# Peripherals.net
KiCad netlist of a schematic drawn in Altium Designer
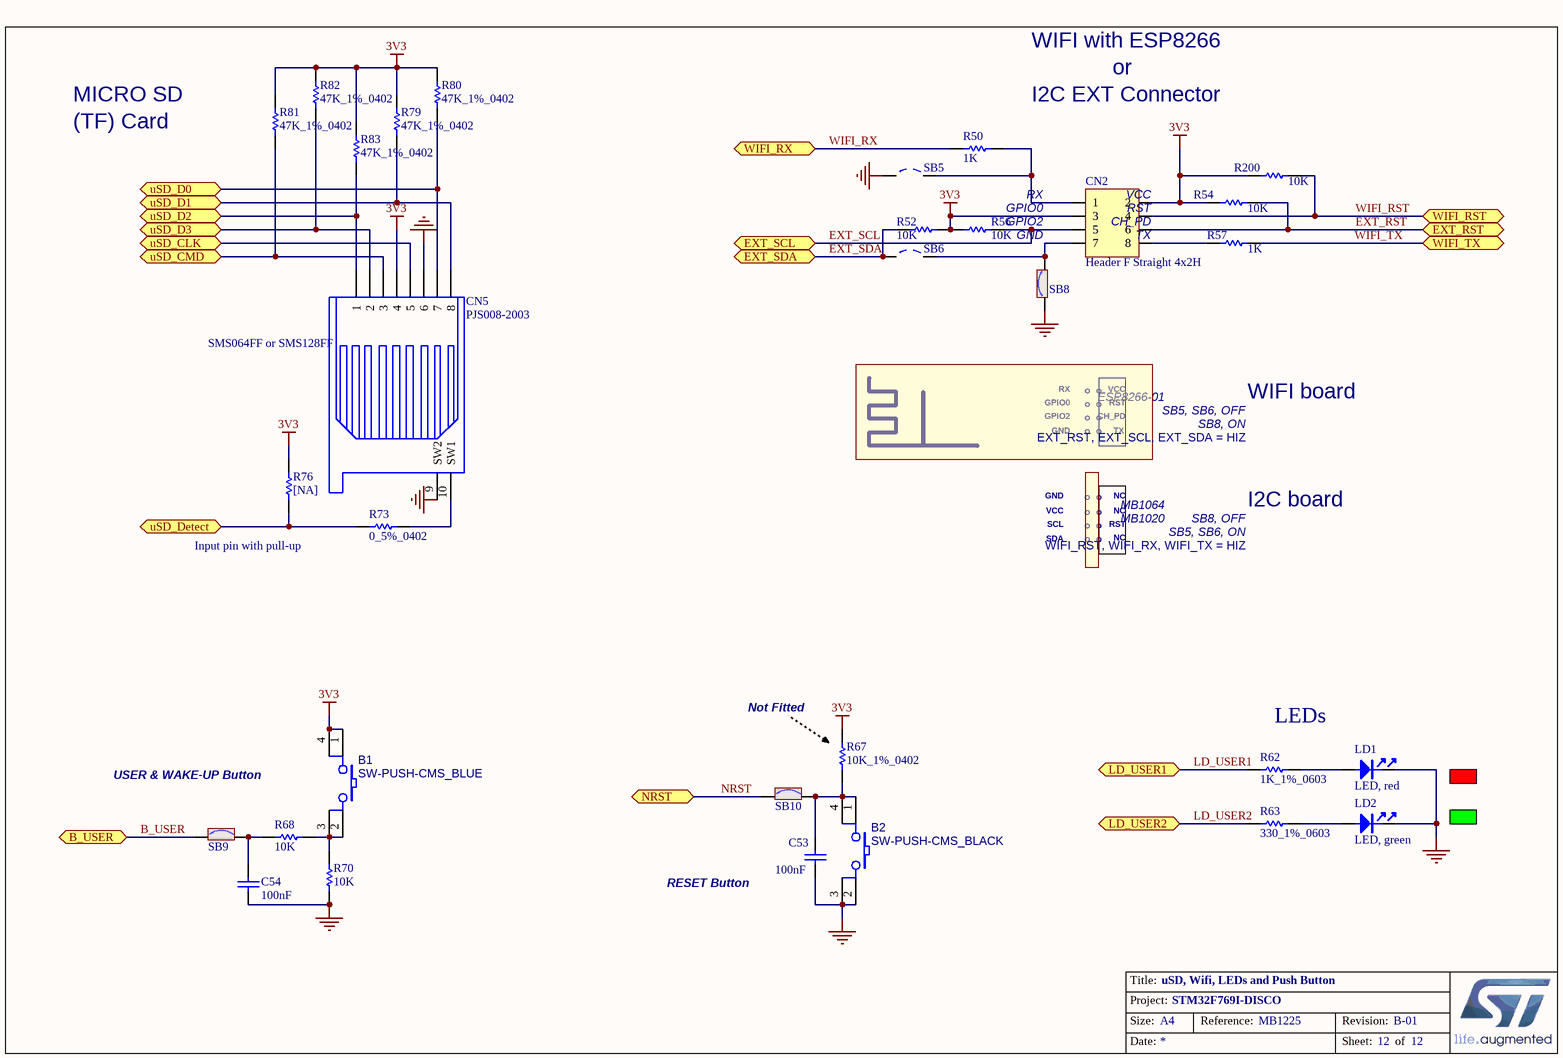
[diagram p0: Peripherals.SchDoc]

(export (version "E")
  (design (tool "Eeschema 10.0.6"))
  (components
    (comp (ref "B1")
      (value "SW-PUSH-CMS_BLUE")
      (footprint "PB10")
      (description "Non-Open Push Button,Blue 0.1A 24V,Square head,6*6,SMT,180Degree,TD-0341X-GO1,wealthmetal")
      (fields (field (name "PROVIDED") "Sub Co"))
      (libsource (lib "MCD_TOOLS_MISCELLANEOUS") (part "SW-PUSH-CMS_BLUE"))
    )
    (comp (ref "B2")
      (value "SW-PUSH-CMS_BLACK")
      (footprint "PB10")
      (description "Non-Open Push Button,Black 0.1A 24V,Square head,6*6,SMT,180Degree,TD-0341X-GO1,wealthmetal")
      (fields (field (name "PROVIDED") "Sub Co"))
      (libsource (lib "MCD_TOOLS_MISCELLANEOUS") (part "SW-PUSH-CMS_BLACK"))
    )
    (comp (ref "C53")
      (value "100nF")
      (footprint "0402C")
      (description "Capacitor,100nF,16V,X7R,10%,0402,YAGEO")
      (libsource (lib "MCD_TOOLS") (part "Cap_100nF_X7R_10%_0402"))
    )
    (comp (ref "C54")
      (value "100nF")
      (footprint "0402C")
      (description "Capacitor,100nF,16V,X7R,10%,0402,YAGEO")
      (libsource (lib "MCD_TOOLS") (part "Cap_100nF_X7R_10%_0402"))
    )
    (comp (ref "CN2")
      (value "Header F Straight 4x2H")
      (footprint "HDR_2X4_2R54")
      (description "Header Female, 4-Pin, Dual row, Straight")
      (libsource (lib "MCD_TOOLS_CONNECTOR") (part "Header 4X2F"))
    )
    (comp (ref "CN5")
      (value "PJS008-2003")
      (footprint "MSD_PJS008_")
      (description "Memory Card Connectors MicroSD Card Conn Revrs Mnt Push-Push")
      (libsource (lib "MCD_TOOLS_CONNECTOR") (part "microSD-PJS008-2003"))
    )
    (comp (ref "LD1")
      (value "LED, red")
      (footprint "0603D")
      (description "LED,red,0603,19-213-R6C-AP1Q2B/3T,everlight")
      (libsource (lib "MCD_TOOLS_MISCELLANEOUS") (part "LED_red"))
    )
    (comp (ref "LD2")
      (value "LED, green")
      (footprint "0603D")
      (description "LED,green,0603,19-213SYGC/S530-E2/TR8,everlight")
      (libsource (lib "MCD_TOOLS_MISCELLANEOUS") (part "LED_green"))
    )
    (comp (ref "R50")
      (value "1K")
      (footprint "0402R")
      (description "Resistor,1K,0402,1%,YAGEO")
      (libsource (lib "MCD_TOOLS_RESISTOR") (part "Res_1K_1%_0402"))
    )
    (comp (ref "R52")
      (value "10K")
      (footprint "0402R")
      (description "Resistor,10K,0402,1%,YAGEO")
      (libsource (lib "MCD_TOOLS") (part "Res_10K_1%_0402"))
    )
    (comp (ref "R54")
      (value "10K")
      (footprint "0402R")
      (description "Resistor,10K,0402,1%,YAGEO")
      (libsource (lib "MCD_TOOLS") (part "Res_10K_1%_0402"))
    )
    (comp (ref "R56")
      (value "10K")
      (footprint "0402R")
      (description "Resistor,10K,0402,1%,YAGEO")
      (libsource (lib "MCD_TOOLS") (part "Res_10K_1%_0402"))
    )
    (comp (ref "R57")
      (value "1K")
      (footprint "0402R")
      (description "Resistor,1K,0402,1%,YAGEO")
      (libsource (lib "MCD_TOOLS_RESISTOR") (part "Res_1K_1%_0402"))
    )
    (comp (ref "R62")
      (value "1K_1%_0603")
      (footprint "0603R")
      (description "Resistor,1K,0603,1%,YAGEO")
      (libsource (lib "MCD_TOOLS_RESISTOR") (part "Res_1K_1%_0603"))
    )
    (comp (ref "R63")
      (value "330_1%_0603")
      (footprint "0603R")
      (description "Resistor,330,0603,1%,YAGEO")
      (libsource (lib "MCD_TOOLS_RESISTOR") (part "Res_330_1%_0603"))
    )
    (comp (ref "R67")
      (value "10K_1%_0402")
      (footprint "0402R")
      (description "Resistor,10K,0402,1%,YAGEO")
      (libsource (lib "MCD_TOOLS") (part "Res_10K_1%_0402"))
    )
    (comp (ref "R68")
      (value "10K")
      (footprint "0402R")
      (description "Resistor,10K,0402,1%,YAGEO")
      (libsource (lib "MCD_TOOLS") (part "Res_10K_1%_0402"))
    )
    (comp (ref "R70")
      (value "10K")
      (footprint "0402R")
      (description "Resistor,10K,0402,1%,YAGEO")
      (libsource (lib "MCD_TOOLS") (part "Res_10K_1%_0402"))
    )
    (comp (ref "R73")
      (value "0_5%_0402")
      (footprint "0402R")
      (description "Resistor,0,0402,5%,YAGEO")
      (libsource (lib "MCD_TOOLS") (part "Res_0_5%_0402"))
    )
    (comp (ref "R76")
      (value "[NA]")
      (footprint "0402R")
      (description "Resistor,[NA],0402")
      (libsource (lib "MCD_TOOLS") (part "Res_NA_0402"))
    )
    (comp (ref "R79")
      (value "47K_1%_0402")
      (footprint "0402R")
      (description "Resistor,47K,0402,1%,YAGEO")
      (libsource (lib "MCD_TOOLS") (part "Res_47K_1%_0402"))
    )
    (comp (ref "R80")
      (value "47K_1%_0402")
      (footprint "0402R")
      (description "Resistor,47K,0402,1%,YAGEO")
      (libsource (lib "MCD_TOOLS") (part "Res_47K_1%_0402"))
    )
    (comp (ref "R81")
      (value "47K_1%_0402")
      (footprint "0402R")
      (description "Resistor,47K,0402,1%,YAGEO")
      (libsource (lib "MCD_TOOLS") (part "Res_47K_1%_0402"))
    )
    (comp (ref "R82")
      (value "47K_1%_0402")
      (footprint "0402R")
      (description "Resistor,47K,0402,1%,YAGEO")
      (libsource (lib "MCD_TOOLS") (part "Res_47K_1%_0402"))
    )
    (comp (ref "R83")
      (value "47K_1%_0402")
      (footprint "0402R")
      (description "Resistor,47K,0402,1%,YAGEO")
      (libsource (lib "MCD_TOOLS") (part "Res_47K_1%_0402"))
    )
    (comp (ref "R200")
      (value "10K")
      (footprint "0402R")
      (description "Resistor,10K,0402,1%,YAGEO")
      (libsource (lib "MCD_TOOLS") (part "Res_10K_1%_0402"))
    )
    (comp (ref "SB5")
      (value "Solder Bridge OFF")
      (footprint "JP2_SMD")
      (libsource (lib "MCD_TOOLS") (part "SB_OFF"))
    )
    (comp (ref "SB6")
      (value "Solder Bridge OFF")
      (footprint "JP2_SMD")
      (libsource (lib "MCD_TOOLS") (part "SB_OFF"))
    )
    (comp (ref "SB8") (value "Solder Bridge ON") (footprint "JP2_SMD") (libsource (lib "") (part "SB_ON_1")))
    (comp (ref "SB9")
      (value "Solder Bridge ON")
      (footprint "JP2_SMD")
      (libsource (lib "MCD_TOOLS") (part "SB_ON"))
    )
    (comp (ref "SB10")
      (value "Solder Bridge ON")
      (footprint "JP2_SMD")
      (libsource (lib "MCD_TOOLS") (part "SB_ON"))
    )
  )
  (nets
    (net (code "1") (name "/B_USER") (class "Default")
      (node (ref "SB9") (pin "1") (pinfunction "1_1") (pintype "passive"))
    )
    (net (code "2") (name "/EXT_RST") (class "Default")
      (node (ref "CN2") (pin "6") (pinfunction "6_6") (pintype "passive"))
      (node (ref "R54") (pin "2") (pinfunction "2_2") (pintype "passive"))
    )
    (net (code "3") (name "/EXT_SCL") (class "Default")
      (node (ref "CN2") (pin "5") (pinfunction "5_5") (pintype "passive"))
      (node (ref "R56") (pin "2") (pinfunction "2_2") (pintype "passive"))
    )
    (net (code "4") (name "/EXT_SDA") (class "Default")
      (node (ref "R52") (pin "1") (pinfunction "1_1") (pintype "passive"))
      (node (ref "SB6") (pin "1") (pinfunction "1_1") (pintype "passive"))
    )
    (net (code "5") (name "/LD_USER1") (class "Default")
      (node (ref "R62") (pin "1") (pinfunction "1_1") (pintype "passive"))
    )
    (net (code "6") (name "/LD_USER2") (class "Default")
      (node (ref "R63") (pin "1") (pinfunction "1_1") (pintype "passive"))
    )
    (net (code "7") (name "/NRST") (class "Default")
      (node (ref "SB10") (pin "1") (pinfunction "1_1") (pintype "passive"))
    )
    (net (code "8") (name "/WIFI_RST") (class "Default")
      (node (ref "CN2") (pin "4") (pinfunction "4_4") (pintype "passive"))
      (node (ref "R200") (pin "2") (pinfunction "2_2") (pintype "passive"))
    )
    (net (code "9") (name "/WIFI_RX") (class "Default")
      (node (ref "R50") (pin "1") (pinfunction "1_1") (pintype "passive"))
    )
    (net (code "10") (name "/WIFI_TX") (class "Default")
      (node (ref "R57") (pin "2") (pinfunction "2_2") (pintype "passive"))
    )
    (net (code "11") (name "/uSD_CLK") (class "Default")
      (node (ref "CN5") (pin "5") (pinfunction "5_5") (pintype "passive"))
    )
    (net (code "12") (name "/uSD_CMD") (class "Default")
      (node (ref "CN5") (pin "3") (pinfunction "3_3") (pintype "passive"))
      (node (ref "R81") (pin "1") (pinfunction "1_1") (pintype "passive"))
    )
    (net (code "13") (name "/uSD_D0") (class "Default")
      (node (ref "CN5") (pin "7") (pinfunction "7_7") (pintype "passive"))
      (node (ref "R80") (pin "1") (pinfunction "1_1") (pintype "passive"))
    )
    (net (code "14") (name "/uSD_D1") (class "Default")
      (node (ref "CN5") (pin "8") (pinfunction "8_8") (pintype "passive"))
      (node (ref "R79") (pin "1") (pinfunction "1_1") (pintype "passive"))
    )
    (net (code "15") (name "/uSD_D2") (class "Default")
      (node (ref "CN5") (pin "1") (pinfunction "1_1") (pintype "passive"))
      (node (ref "R83") (pin "1") (pinfunction "1_1") (pintype "passive"))
    )
    (net (code "16") (name "/uSD_D3") (class "Default")
      (node (ref "CN5") (pin "2") (pinfunction "2_2") (pintype "passive"))
      (node (ref "R82") (pin "1") (pinfunction "1_1") (pintype "passive"))
    )
    (net (code "17") (name "/uSD_Detect") (class "Default")
      (node (ref "R73") (pin "1") (pinfunction "1_1") (pintype "passive"))
      (node (ref "R76") (pin "1") (pinfunction "1_1") (pintype "passive"))
    )
    (net (code "18") (name "3V3") (class "Default")
      (node (ref "B1") (pin "1") (pinfunction "1_1") (pintype "passive"))
      (node (ref "B1") (pin "4") (pinfunction "4_4") (pintype "passive"))
      (node (ref "CN2") (pin "2") (pinfunction "2_2") (pintype "passive"))
      (node (ref "CN2") (pin "3") (pinfunction "3_3") (pintype "passive"))
      (node (ref "CN5") (pin "4") (pinfunction "4_4") (pintype "passive"))
      (node (ref "R200") (pin "1") (pinfunction "1_1") (pintype "passive"))
      (node (ref "R52") (pin "2") (pinfunction "2_2") (pintype "passive"))
      (node (ref "R54") (pin "1") (pinfunction "1_1") (pintype "passive"))
      (node (ref "R56") (pin "1") (pinfunction "1_1") (pintype "passive"))
      (node (ref "R67") (pin "2") (pinfunction "2_2") (pintype "passive"))
      (node (ref "R76") (pin "2") (pinfunction "2_2") (pintype "passive"))
      (node (ref "R79") (pin "2") (pinfunction "2_2") (pintype "passive"))
      (node (ref "R80") (pin "2") (pinfunction "2_2") (pintype "passive"))
      (node (ref "R81") (pin "2") (pinfunction "2_2") (pintype "passive"))
      (node (ref "R82") (pin "2") (pinfunction "2_2") (pintype "passive"))
      (node (ref "R83") (pin "2") (pinfunction "2_2") (pintype "passive"))
    )
    (net (code "19") (name "GND") (class "Default")
      (node (ref "B2") (pin "2") (pinfunction "2_2") (pintype "passive"))
      (node (ref "B2") (pin "3") (pinfunction "3_3") (pintype "passive"))
      (node (ref "C53") (pin "1") (pinfunction "1_1") (pintype "passive"))
      (node (ref "C54") (pin "1") (pinfunction "1_1") (pintype "passive"))
      (node (ref "CN5") (pin "6") (pinfunction "6_6") (pintype "passive"))
      (node (ref "CN5") (pin "9") (pinfunction "SW2_9") (pintype "passive"))
      (node (ref "LD1") (pin "2") (pintype "passive"))
      (node (ref "LD2") (pin "2") (pintype "passive"))
      (node (ref "R70") (pin "1") (pinfunction "1_1") (pintype "passive"))
      (node (ref "SB5") (pin "1") (pinfunction "1_1") (pintype "passive"))
      (node (ref "SB8") (pin "1") (pinfunction "1_1") (pintype "passive"))
    )
    (net (code "20") (name "Net-(B1-Pad2)") (class "Default")
      (node (ref "B1") (pin "2") (pinfunction "2_2") (pintype "passive"))
      (node (ref "B1") (pin "3") (pinfunction "3_3") (pintype "passive"))
      (node (ref "R68") (pin "2") (pinfunction "2_2") (pintype "passive"))
      (node (ref "R70") (pin "2") (pinfunction "2_2") (pintype "passive"))
    )
    (net (code "21") (name "Net-(B2-Pad1)") (class "Default")
      (node (ref "B2") (pin "1") (pinfunction "1_1") (pintype "passive"))
      (node (ref "B2") (pin "4") (pinfunction "4_4") (pintype "passive"))
      (node (ref "C53") (pin "2") (pinfunction "2_2") (pintype "passive"))
      (node (ref "R67") (pin "1") (pinfunction "1_1") (pintype "passive"))
      (node (ref "SB10") (pin "2") (pinfunction "2_2") (pintype "passive"))
    )
    (net (code "22") (name "Net-(C54-Pad2)") (class "Default")
      (node (ref "C54") (pin "2") (pinfunction "2_2") (pintype "passive"))
      (node (ref "R68") (pin "1") (pinfunction "1_1") (pintype "passive"))
      (node (ref "SB9") (pin "2") (pinfunction "2_2") (pintype "passive"))
    )
    (net (code "23") (name "Net-(CN2-Pad1)") (class "Default")
      (node (ref "CN2") (pin "1") (pinfunction "1_1") (pintype "passive"))
      (node (ref "R50") (pin "2") (pinfunction "2_2") (pintype "passive"))
      (node (ref "SB5") (pin "2") (pinfunction "2_2") (pintype "passive"))
    )
    (net (code "24") (name "Net-(CN2-Pad7)") (class "Default")
      (node (ref "CN2") (pin "7") (pinfunction "7_7") (pintype "passive"))
      (node (ref "SB6") (pin "2") (pinfunction "2_2") (pintype "passive"))
      (node (ref "SB8") (pin "2") (pinfunction "2_2") (pintype "passive"))
    )
    (net (code "25") (name "Net-(CN2-Pad8)") (class "Default")
      (node (ref "CN2") (pin "8") (pinfunction "8_8") (pintype "passive"))
      (node (ref "R57") (pin "1") (pinfunction "1_1") (pintype "passive"))
    )
    (net (code "26") (name "Net-(CN5-SW1)") (class "Default")
      (node (ref "CN5") (pin "10") (pinfunction "SW1_10") (pintype "passive"))
      (node (ref "R73") (pin "2") (pinfunction "2_2") (pintype "passive"))
    )
    (net (code "27") (name "Net-(LD1-Pad1)") (class "Default")
      (node (ref "LD1") (pin "1") (pintype "passive"))
      (node (ref "R62") (pin "2") (pinfunction "2_2") (pintype "passive"))
    )
    (net (code "28") (name "Net-(LD2-Pad1)") (class "Default")
      (node (ref "LD2") (pin "1") (pintype "passive"))
      (node (ref "R63") (pin "2") (pinfunction "2_2") (pintype "passive"))
    )
  )
)
